# Top.net
KiCad netlist of a schematic drawn in Altium Designer
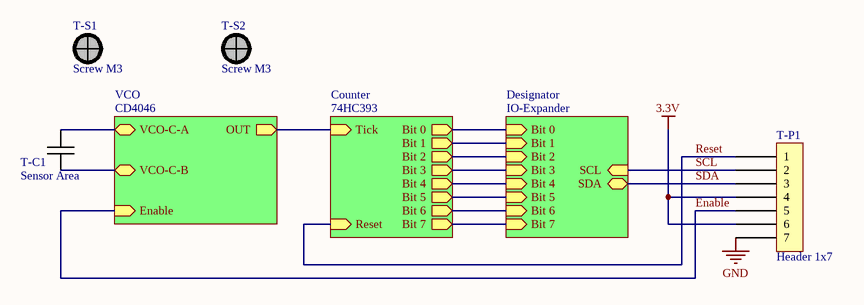
[diagram p0: Top.SchDoc]

(export (version "E")
  (design (tool "Eeschema 10.0.6"))
  (components
    (comp (ref "T-C1") (value "Sensor Area") (libsource (lib "Standard") (part "Capacitor")))
    (comp (ref "T-P1")
      (value "Header 1x7")
      (footprint "Header 1x7")
      (libsource (lib "Headers") (part "Header 1x7"))
    )
    (comp (ref "T-S1")
      (value "Screw M3")
      (footprint "Screw M3")
      (libsource (lib "Mechanical") (part "Screw M3"))
    )
    (comp (ref "T-S2")
      (value "Screw M3")
      (footprint "Screw M3")
      (libsource (lib "Mechanical") (part "Screw M3"))
    )
  )
  (nets
    (net (code "9") (name "/Enable") (class "Default")
      (node (ref "T-P1") (pin "5") (pinfunction "5_5") (pintype "passive"))
    )
    (net (code "11") (name "/Reset") (class "Default")
      (node (ref "T-P1") (pin "1") (pinfunction "1_1") (pintype "passive"))
    )
    (net (code "12") (name "/SCL") (class "Default")
      (node (ref "T-P1") (pin "2") (pinfunction "2_2") (pintype "passive"))
    )
    (net (code "13") (name "/SDA") (class "Default")
      (node (ref "T-P1") (pin "3") (pinfunction "3_3") (pintype "passive"))
    )
    (net (code "14") (name "/VCO-C-A") (class "Default")
      (node (ref "T-C1") (pin "1") (pinfunction "1_1") (pintype "passive"))
    )
    (net (code "15") (name "/VCO-C-B") (class "Default")
      (node (ref "T-C1") (pin "2") (pinfunction "1_2") (pintype "passive"))
    )
    (net (code "16") (name "3.3V") (class "Default")
      (node (ref "T-P1") (pin "4") (pinfunction "4_4") (pintype "passive"))
      (node (ref "T-P1") (pin "6") (pinfunction "6_6") (pintype "passive"))
    )
    (net (code "17") (name "GND") (class "Default")
      (node (ref "T-P1") (pin "7") (pinfunction "7_7") (pintype "passive"))
    )
  )
)
